# Data_East_converter.net
KiCad netlist of a schematic drawn in EAGLE
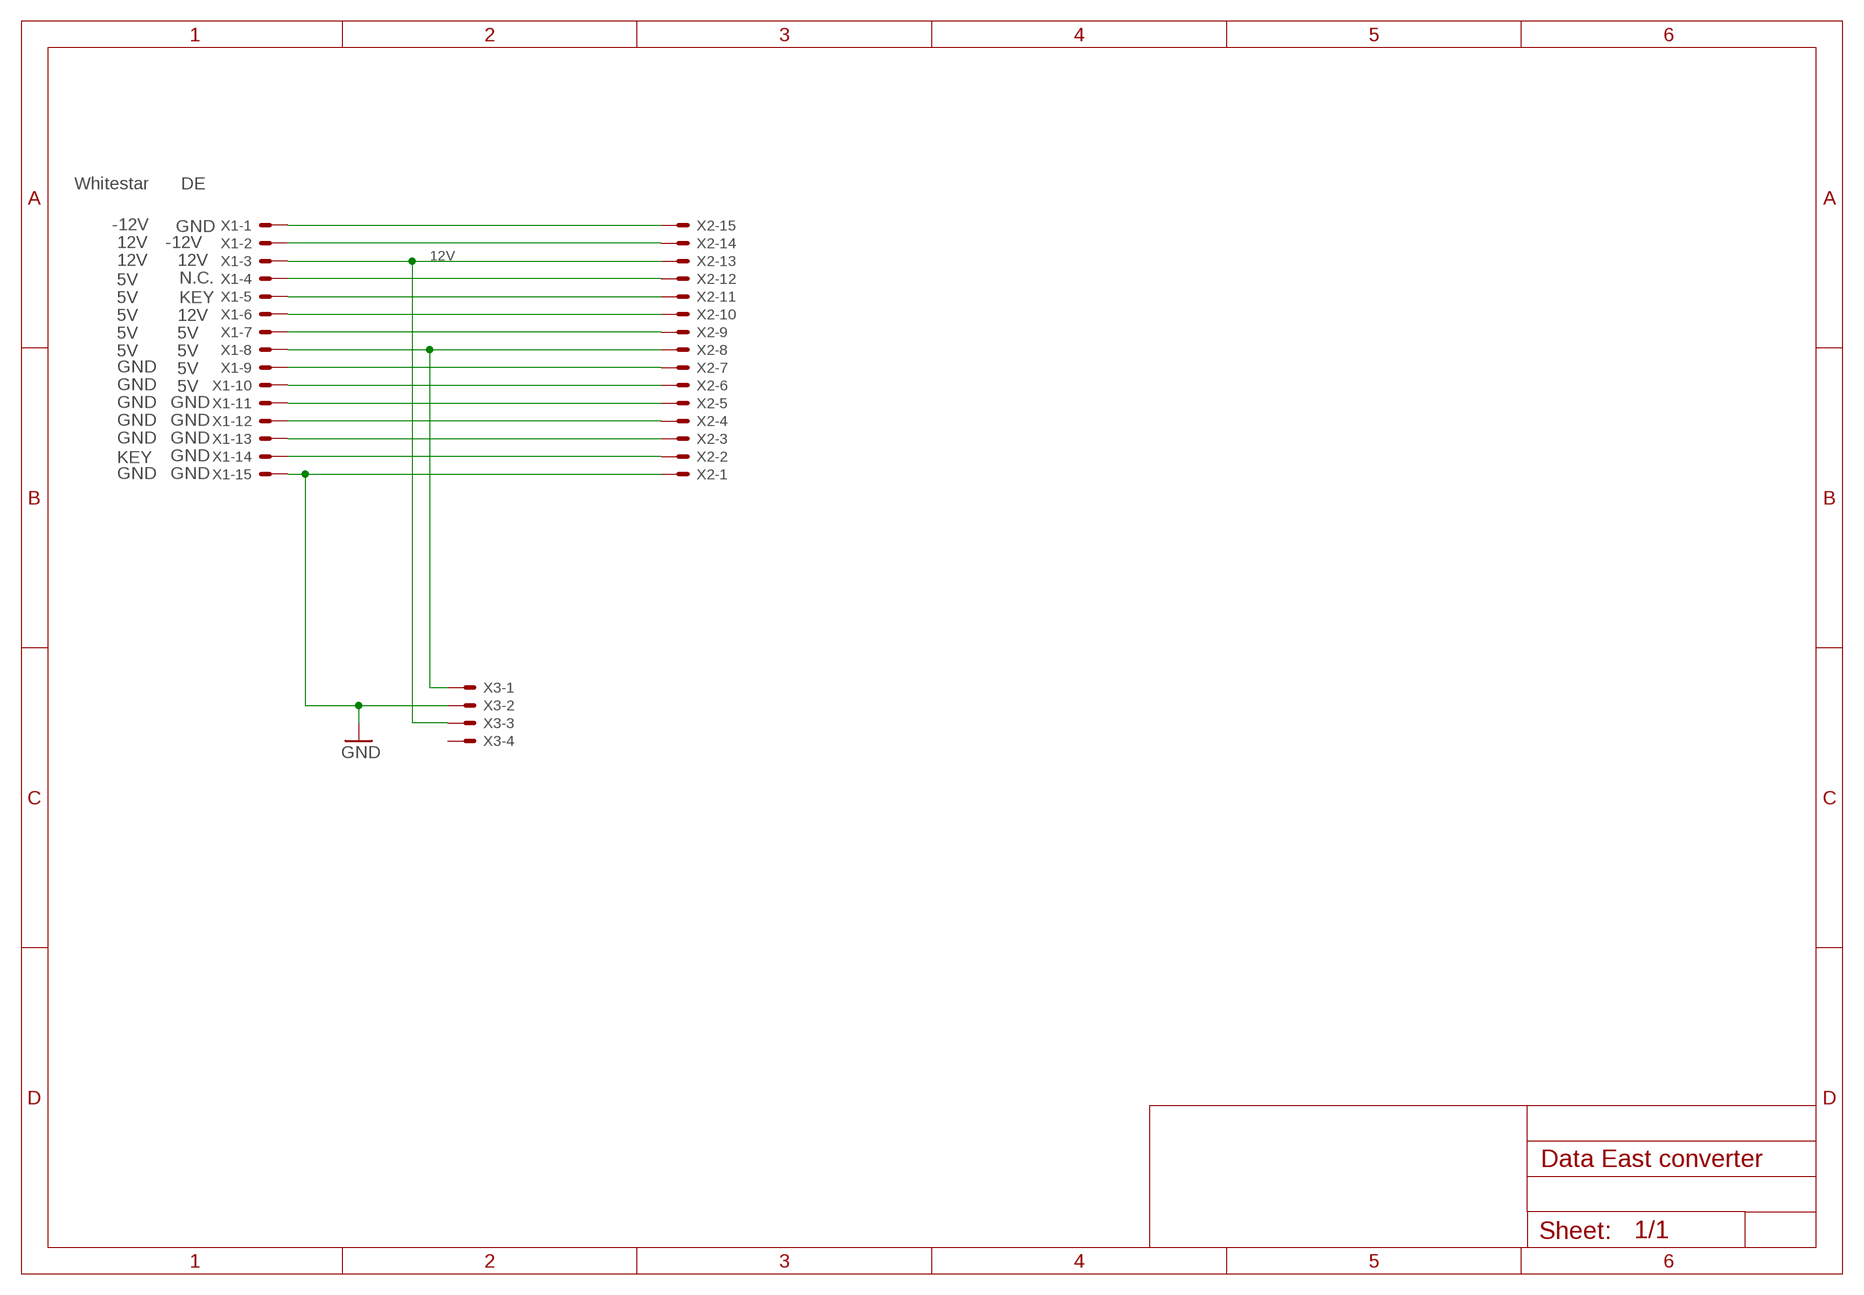
[diagram p0: schematic, sheet 1]

(export (version "E")
  (design (tool "Eeschema 10.0.6"))
  (components
    (comp (ref "X1")
      (value "KK-156-15_FKK-156-15-F")
      (footprint "eagle-import:KK-156-15_F")
      (libsource (lib "eagle-import") (part "KK-156-15_FKK-156-15-F"))
    )
    (comp (ref "X2")
      (value "KK-156-15")
      (footprint "eagle-import:KK-156-15")
      (fields (field (name "MF") "MOLEX"))
      (libsource (lib "eagle-import") (part "KK-156-15"))
    )
    (comp (ref "X3")
      (value "KK-156-4")
      (footprint "eagle-import:KK-156-4")
      (fields (field (name "MF") "MOLEX"))
      (libsource (lib "eagle-import") (part "KK-156-4"))
    )
  )
  (nets
    (net (code "1") (name "/12V") (class "Default")
      (node (ref "X1") (pin "3") (pinfunction "S_3") (pintype "passive"))
      (node (ref "X2") (pin "13") (pinfunction "S_13") (pintype "passive"))
      (node (ref "X3") (pin "3") (pinfunction "S_3") (pintype "passive"))
    )
    (net (code "2") (name "GND") (class "Default")
      (node (ref "X1") (pin "15") (pinfunction "S_15") (pintype "passive"))
      (node (ref "X2") (pin "1") (pinfunction "S_1") (pintype "passive"))
      (node (ref "X3") (pin "2") (pinfunction "S_2") (pintype "passive"))
    )
    (net (code "3") (name "Net-(X1A-S)") (class "Default")
      (node (ref "X1") (pin "1") (pinfunction "S_1") (pintype "passive"))
      (node (ref "X2") (pin "15") (pinfunction "S_15") (pintype "passive"))
    )
    (net (code "4") (name "Net-(X1B-S)") (class "Default")
      (node (ref "X1") (pin "10") (pinfunction "S_10") (pintype "passive"))
      (node (ref "X2") (pin "6") (pinfunction "S_6") (pintype "passive"))
    )
    (net (code "5") (name "Net-(X1C-S)") (class "Default")
      (node (ref "X1") (pin "11") (pinfunction "S_11") (pintype "passive"))
      (node (ref "X2") (pin "5") (pinfunction "S_5") (pintype "passive"))
    )
    (net (code "6") (name "Net-(X1D-S)") (class "Default")
      (node (ref "X1") (pin "12") (pinfunction "S_12") (pintype "passive"))
      (node (ref "X2") (pin "4") (pinfunction "S_4") (pintype "passive"))
    )
    (net (code "7") (name "Net-(X1E-S)") (class "Default")
      (node (ref "X1") (pin "13") (pinfunction "S_13") (pintype "passive"))
      (node (ref "X2") (pin "3") (pinfunction "S_3") (pintype "passive"))
    )
    (net (code "8") (name "Net-(X1F-S)") (class "Default")
      (node (ref "X1") (pin "14") (pinfunction "S_14") (pintype "passive"))
      (node (ref "X2") (pin "2") (pinfunction "S_2") (pintype "passive"))
    )
    (net (code "9") (name "Net-(X1H-S)") (class "Default")
      (node (ref "X1") (pin "2") (pinfunction "S_2") (pintype "passive"))
      (node (ref "X2") (pin "14") (pinfunction "S_14") (pintype "passive"))
    )
    (net (code "10") (name "Net-(X1J-S)") (class "Default")
      (node (ref "X1") (pin "4") (pinfunction "S_4") (pintype "passive"))
      (node (ref "X2") (pin "12") (pinfunction "S_12") (pintype "passive"))
    )
    (net (code "11") (name "Net-(X1K-S)") (class "Default")
      (node (ref "X1") (pin "5") (pinfunction "S_5") (pintype "passive"))
      (node (ref "X2") (pin "11") (pinfunction "S_11") (pintype "passive"))
    )
    (net (code "12") (name "Net-(X1L-S)") (class "Default")
      (node (ref "X1") (pin "6") (pinfunction "S_6") (pintype "passive"))
      (node (ref "X2") (pin "10") (pinfunction "S_10") (pintype "passive"))
    )
    (net (code "13") (name "Net-(X1M-S)") (class "Default")
      (node (ref "X1") (pin "7") (pinfunction "S_7") (pintype "passive"))
      (node (ref "X2") (pin "9") (pinfunction "S_9") (pintype "passive"))
    )
    (net (code "14") (name "Net-(X1N-S)") (class "Default")
      (node (ref "X1") (pin "8") (pinfunction "S_8") (pintype "passive"))
      (node (ref "X2") (pin "8") (pinfunction "S_8") (pintype "passive"))
      (node (ref "X3") (pin "1") (pinfunction "S_1") (pintype "passive"))
    )
    (net (code "15") (name "Net-(X1O-S)") (class "Default")
      (node (ref "X1") (pin "9") (pinfunction "S_9") (pintype "passive"))
      (node (ref "X2") (pin "7") (pinfunction "S_7") (pintype "passive"))
    )
    (net (code "16") (name "unconnected-(X3D-S-Pad4)") (class "Default")
      (node (ref "X3") (pin "4") (pinfunction "S_4") (pintype "passive"))
    )
  )
)
